# design.net
KiCad netlist of a schematic drawn in Altium Designer
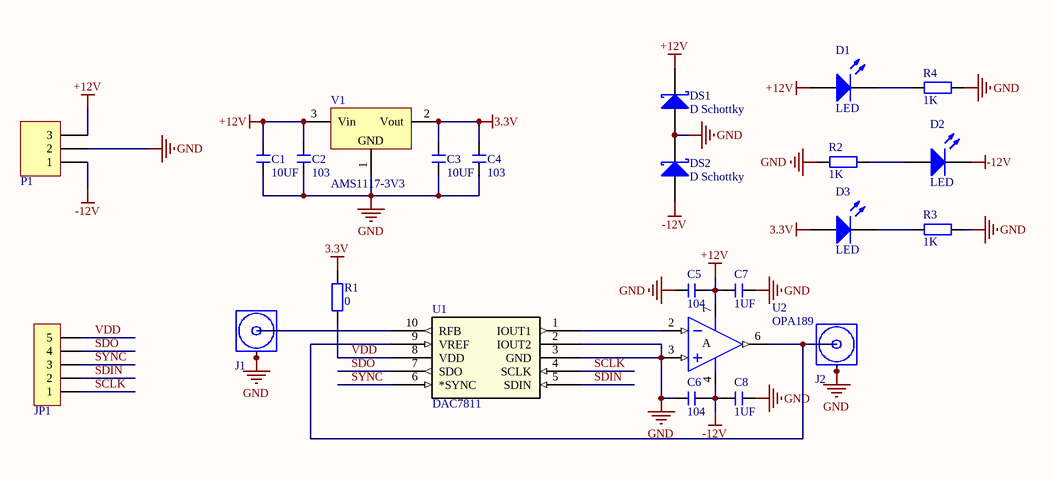
[diagram p0: 程控放大器.SchDoc]

(export (version "E")
  (design (tool "Eeschema 10.0.6"))
  (components
    (comp (ref "C1")
      (value "10UF")
      (footprint "C 0805")
      (description "无极性贴片电容")
      (fields (field (name "版权归属") "源创客"))
      (libsource (lib "电阻-电容-电感") (part "C"))
    )
    (comp (ref "C2")
      (value "103")
      (footprint "C 0603")
      (description "无极性贴片电容")
      (fields (field (name "版权归属") "源创客"))
      (libsource (lib "电阻-电容-电感") (part "C"))
    )
    (comp (ref "C3")
      (value "10UF")
      (footprint "C 0805")
      (description "无极性贴片电容")
      (fields (field (name "版权归属") "源创客"))
      (libsource (lib "电阻-电容-电感") (part "C"))
    )
    (comp (ref "C4")
      (value "103")
      (footprint "C 0603")
      (description "无极性贴片电容")
      (fields (field (name "版权归属") "源创客"))
      (libsource (lib "电阻-电容-电感") (part "C"))
    )
    (comp (ref "C5")
      (value "104")
      (footprint "C 0805")
      (description "无极性贴片电容")
      (fields (field (name "版权归属") "源创客"))
      (libsource (lib "电阻-电容-电感") (part "C"))
    )
    (comp (ref "C6")
      (value "104")
      (footprint "C 0805")
      (description "无极性贴片电容")
      (fields (field (name "版权归属") "源创客"))
      (libsource (lib "电阻-电容-电感") (part "C"))
    )
    (comp (ref "C7")
      (value "1UF")
      (footprint "C 0805")
      (description "无极性贴片电容")
      (fields (field (name "版权归属") "源创客"))
      (libsource (lib "电阻-电容-电感") (part "C"))
    )
    (comp (ref "C8")
      (value "1UF")
      (footprint "C 0805")
      (description "无极性贴片电容")
      (fields (field (name "版权归属") "源创客"))
      (libsource (lib "电阻-电容-电感") (part "C"))
    )
    (comp (ref "D1")
      (value "LED")
      (footprint "LED_0805")
      (description "发光二极管")
      (fields (field (name "PUBLISHER") "Altium Limited"))
      (libsource (lib "LIB") (part "LED"))
    )
    (comp (ref "D2")
      (value "LED")
      (footprint "LED_0805")
      (description "发光二极管")
      (fields (field (name "PUBLISHER") "Altium Limited"))
      (libsource (lib "LIB") (part "LED"))
    )
    (comp (ref "D3")
      (value "LED")
      (footprint "LED_0805")
      (description "发光二极管")
      (fields (field (name "PUBLISHER") "Altium Limited"))
      (libsource (lib "LIB") (part "LED"))
    )
    (comp (ref "DS1")
      (value "D Schottky")
      (footprint "DIODE-SMA")
      (description "Schottky Diode")
      (fields (field (name "PUBLISHER") "Altium Limited"))
      (libsource (lib "LIB") (part "D Schottky"))
    )
    (comp (ref "DS2")
      (value "D Schottky")
      (footprint "DIODE-SMA")
      (description "Schottky Diode")
      (fields (field (name "PUBLISHER") "Altium Limited"))
      (libsource (lib "LIB") (part "D Schottky"))
    )
    (comp (ref "J1") (value "COAX") (footprint "MCX5.08-5-H") (libsource (lib "LIB") (part "COAX")))
    (comp (ref "J2") (value "COAX") (footprint "MCX5.08-5-H") (libsource (lib "LIB") (part "COAX")))
    (comp (ref "JP1")
      (value "HDR-1X5")
      (footprint "HDR-1X5")
      (description "5P接插件")
      (fields (field (name "版权归属") "源创客"))
      (libsource (lib "接插件") (part "Header 5"))
    )
    (comp (ref "P1")
      (value "Header 3")
      (footprint "HDR3X1_B2")
      (description "接插件")
      (fields (field (name "PUBLISHER") "Altium Limited"))
      (libsource (lib "LIB") (part "Header 3"))
    )
    (comp (ref "R1")
      (value "0")
      (footprint "R 0603")
      (description "贴片电阻")
      (fields (field (name "版权归属") "源创客"))
      (libsource (lib "电阻-电容-电感") (part "R"))
    )
    (comp (ref "R2")
      (value "1K")
      (footprint "R 0805")
      (description "贴片电阻")
      (fields (field (name "版权归属") "源创客"))
      (libsource (lib "电阻-电容-电感") (part "R"))
    )
    (comp (ref "R3")
      (value "1K")
      (footprint "R 0805")
      (description "贴片电阻")
      (fields (field (name "版权归属") "源创客"))
      (libsource (lib "电阻-电容-电感") (part "R"))
    )
    (comp (ref "R4")
      (value "1K")
      (footprint "R 0805")
      (description "贴片电阻")
      (fields (field (name "版权归属") "源创客"))
      (libsource (lib "电阻-电容-电感") (part "R"))
    )
    (comp (ref "U1")
      (value "DAC7811")
      (footprint "VSSOP 10 (DGK)")
      (description "12-Bit, Serial Input, Multiplying Digital-to-Analog Converter")
      (fields
        (field (name "MANUFACTURER") "Texas Instruments")
        (field (name "MANUFACTURER_PART_NUMBER") "dac7811_dgs_10")
      )
      (libsource (lib "LIB") (part "DAC7811"))
    )
    (comp (ref "U2")
      (value "OPA189")
      (footprint "SOIC8_N")
      (description "支持多路复用器的 14MHz、低噪声、零漂移、RRO、CMOS 精密运算放大器")
      (libsource (lib "LIB") (part "OPA189"))
    )
    (comp (ref "V1")
      (value "AMS1117-3V3")
      (footprint "SOT223_L")
      (description "三端稳压芯片")
      (fields (field (name "版权归属") "源创客"))
      (libsource (lib "IC芯片") (part "AMS1117"))
    )
  )
  (nets
    (net (code "1") (name "+12V") (class "Default")
      (node (ref "C1") (pin "1") (pinfunction "1_1") (pintype "passive"))
      (node (ref "C2") (pin "1") (pinfunction "1_1") (pintype "passive"))
      (node (ref "C5") (pin "2") (pinfunction "2_2") (pintype "passive"))
      (node (ref "C7") (pin "1") (pinfunction "1_1") (pintype "passive"))
      (node (ref "D1") (pin "1") (pinfunction "A_1") (pintype "passive"))
      (node (ref "DS1") (pin "2") (pinfunction "2_2") (pintype "passive"))
      (node (ref "P1") (pin "3") (pinfunction "3_3") (pintype "passive"))
      (node (ref "U2") (pin "7") (pinfunction "V+_7") (pintype "power_in"))
      (node (ref "V1") (pin "3") (pinfunction "Vin_3") (pintype "passive"))
    )
    (net (code "2") (name "-12V") (class "Default")
      (node (ref "C6") (pin "2") (pinfunction "2_2") (pintype "passive"))
      (node (ref "C8") (pin "1") (pinfunction "1_1") (pintype "passive"))
      (node (ref "D2") (pin "2") (pinfunction "K_2") (pintype "passive"))
      (node (ref "DS2") (pin "1") (pinfunction "1_1") (pintype "passive"))
      (node (ref "P1") (pin "1") (pinfunction "1_1") (pintype "passive"))
      (node (ref "U2") (pin "4") (pinfunction "V-_4") (pintype "power_in"))
    )
    (net (code "3") (name "/SCLK") (class "Default")
      (node (ref "JP1") (pin "1") (pinfunction "1_1") (pintype "passive"))
      (node (ref "U1") (pin "4") (pinfunction "SCLK_4") (pintype "input"))
    )
    (net (code "4") (name "/SDIN") (class "Default")
      (node (ref "JP1") (pin "2") (pinfunction "2_2") (pintype "passive"))
      (node (ref "U1") (pin "5") (pinfunction "SDIN_5") (pintype "input"))
    )
    (net (code "5") (name "/SDO") (class "Default")
      (node (ref "JP1") (pin "4") (pinfunction "4_4") (pintype "passive"))
      (node (ref "U1") (pin "7") (pinfunction "SDO_7") (pintype "output"))
    )
    (net (code "6") (name "/SYNC") (class "Default")
      (node (ref "JP1") (pin "3") (pinfunction "3_3") (pintype "passive"))
      (node (ref "U1") (pin "6") (pinfunction "*SYNC_6") (pintype "input"))
    )
    (net (code "7") (name "/VDD") (class "Default")
      (node (ref "JP1") (pin "5") (pinfunction "5_5") (pintype "passive"))
      (node (ref "R1") (pin "1") (pinfunction "1_1") (pintype "passive"))
      (node (ref "U1") (pin "8") (pinfunction "VDD_8") (pintype "power_in"))
    )
    (net (code "8") (name "3.3V") (class "Default")
      (node (ref "C3") (pin "1") (pinfunction "1_1") (pintype "passive"))
      (node (ref "C4") (pin "1") (pinfunction "1_1") (pintype "passive"))
      (node (ref "D3") (pin "1") (pinfunction "A_1") (pintype "passive"))
      (node (ref "R1") (pin "2") (pinfunction "2_2") (pintype "passive"))
      (node (ref "V1") (pin "2") (pinfunction "Vout_2") (pintype "passive"))
    )
    (net (code "9") (name "GND") (class "Default")
      (node (ref "C1") (pin "2") (pinfunction "2_2") (pintype "passive"))
      (node (ref "C2") (pin "2") (pinfunction "2_2") (pintype "passive"))
      (node (ref "C3") (pin "2") (pinfunction "2_2") (pintype "passive"))
      (node (ref "C4") (pin "2") (pinfunction "2_2") (pintype "passive"))
      (node (ref "C5") (pin "1") (pinfunction "1_1") (pintype "passive"))
      (node (ref "C6") (pin "1") (pinfunction "1_1") (pintype "passive"))
      (node (ref "C7") (pin "2") (pinfunction "2_2") (pintype "passive"))
      (node (ref "C8") (pin "2") (pinfunction "2_2") (pintype "passive"))
      (node (ref "DS1") (pin "1") (pinfunction "1_1") (pintype "passive"))
      (node (ref "DS2") (pin "2") (pinfunction "2_2") (pintype "passive"))
      (node (ref "J1") (pin "2") (pinfunction "GND_2") (pintype "passive"))
      (node (ref "J1") (pin "3") (pinfunction "GND_3") (pintype "passive"))
      (node (ref "J1") (pin "4") (pinfunction "GND_4") (pintype "passive"))
      (node (ref "J1") (pin "5") (pinfunction "GND_5") (pintype "passive"))
      (node (ref "J2") (pin "2") (pinfunction "GND_2") (pintype "passive"))
      (node (ref "J2") (pin "3") (pinfunction "GND_3") (pintype "passive"))
      (node (ref "J2") (pin "4") (pinfunction "GND_4") (pintype "passive"))
      (node (ref "J2") (pin "5") (pinfunction "GND_5") (pintype "passive"))
      (node (ref "P1") (pin "2") (pinfunction "2_2") (pintype "passive"))
      (node (ref "R2") (pin "1") (pinfunction "1_1") (pintype "passive"))
      (node (ref "R3") (pin "2") (pinfunction "2_2") (pintype "passive"))
      (node (ref "R4") (pin "2") (pinfunction "2_2") (pintype "passive"))
      (node (ref "U1") (pin "2") (pinfunction "IOUT2_2") (pintype "passive"))
      (node (ref "U1") (pin "3") (pinfunction "GND_3") (pintype "power_in"))
      (node (ref "U2") (pin "3") (pinfunction "+IN_3") (pintype "input"))
      (node (ref "V1") (pin "1") (pinfunction "GND_1") (pintype "passive"))
    )
    (net (code "10") (name "Net-(D1-K)") (class "Default")
      (node (ref "D1") (pin "2") (pinfunction "K_2") (pintype "passive"))
      (node (ref "R4") (pin "1") (pinfunction "1_1") (pintype "passive"))
    )
    (net (code "11") (name "Net-(D2-A)") (class "Default")
      (node (ref "D2") (pin "1") (pinfunction "A_1") (pintype "passive"))
      (node (ref "R2") (pin "2") (pinfunction "2_2") (pintype "passive"))
    )
    (net (code "12") (name "Net-(D3-K)") (class "Default")
      (node (ref "D3") (pin "2") (pinfunction "K_2") (pintype "passive"))
      (node (ref "R3") (pin "1") (pinfunction "1_1") (pintype "passive"))
    )
    (net (code "13") (name "Net-(J1-Signal)") (class "Default")
      (node (ref "J1") (pin "1") (pinfunction "Signal_1") (pintype "passive"))
      (node (ref "U1") (pin "10") (pinfunction "RFB_10") (pintype "output"))
    )
    (net (code "14") (name "Net-(J2-Signal)") (class "Default")
      (node (ref "J2") (pin "1") (pinfunction "Signal_1") (pintype "passive"))
      (node (ref "U1") (pin "9") (pinfunction "VREF_9") (pintype "input"))
      (node (ref "U2") (pin "6") (pinfunction "OUT_6") (pintype "output"))
    )
    (net (code "15") (name "Net-(U1-IOUT1)") (class "Default")
      (node (ref "U1") (pin "1") (pinfunction "IOUT1_1") (pintype "output"))
      (node (ref "U2") (pin "2") (pinfunction "-IN_2") (pintype "input"))
    )
  )
)
